# 3_channel_relay_board.net
KiCad netlist of a schematic drawn in EAGLE
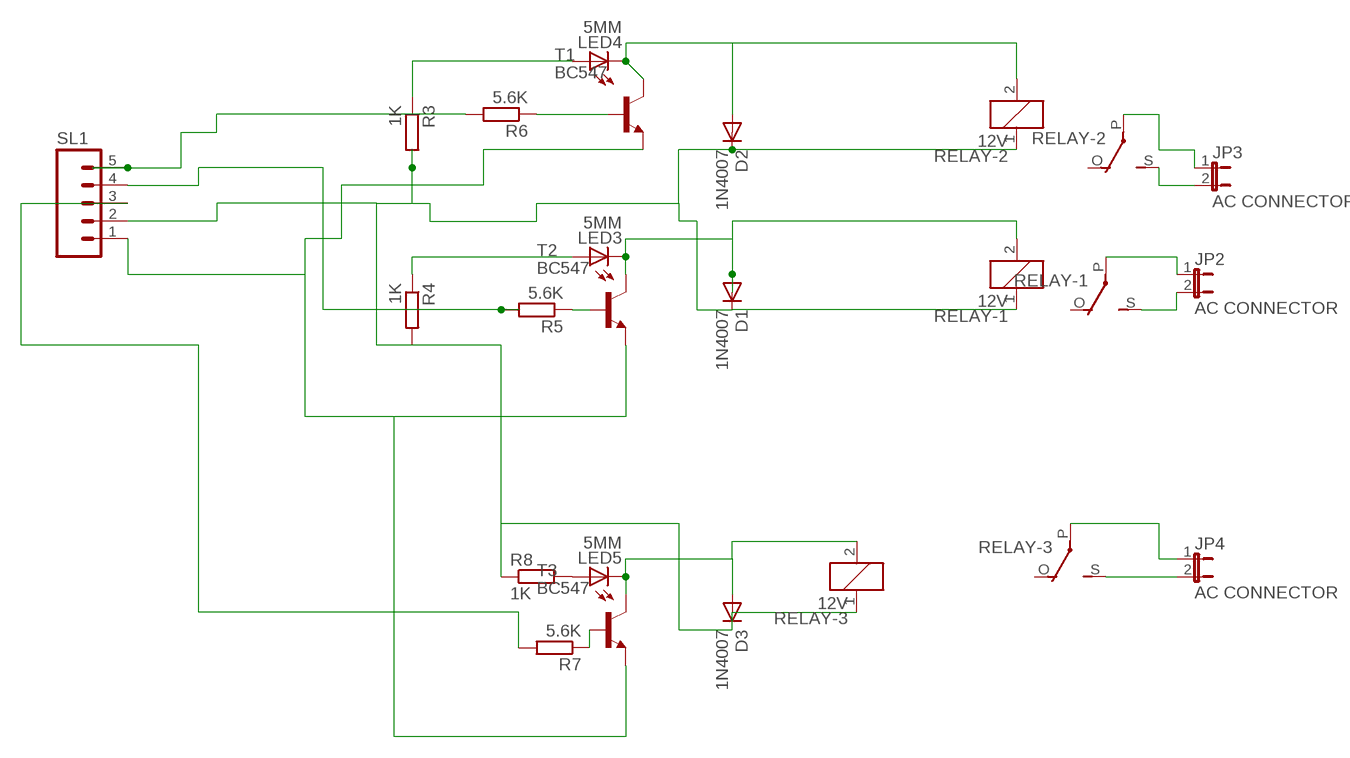
[diagram p0: schematic, sheet 1]

(export (version "E")
  (design (tool "Eeschema 10.0.6"))
  (components
    (comp (ref "D1")
      (value "1N4007")
      (footprint "eagle-import:DO41-10")
      (libsource (lib "eagle-import") (part "1N4004"))
    )
    (comp (ref "D2")
      (value "1N4007")
      (footprint "eagle-import:DO41-10")
      (libsource (lib "eagle-import") (part "1N4004"))
    )
    (comp (ref "D3")
      (value "1N4007")
      (footprint "eagle-import:DO41-10")
      (libsource (lib "eagle-import") (part "1N4004"))
    )
    (comp (ref "JP2")
      (value "AC CONNECTOR")
      (footprint "eagle-import:JP1")
      (libsource (lib "eagle-import") (part "JP1E"))
    )
    (comp (ref "JP3")
      (value "AC CONNECTOR")
      (footprint "eagle-import:JP1")
      (libsource (lib "eagle-import") (part "JP1E"))
    )
    (comp (ref "JP4")
      (value "AC CONNECTOR")
      (footprint "eagle-import:JP1")
      (libsource (lib "eagle-import") (part "JP1E"))
    )
    (comp (ref "LED3")
      (value "5MM")
      (footprint "eagle-import:LED5MM")
      (libsource (lib "eagle-import") (part "LED5MM"))
    )
    (comp (ref "LED4")
      (value "5MM")
      (footprint "eagle-import:LED5MM")
      (libsource (lib "eagle-import") (part "LED5MM"))
    )
    (comp (ref "LED5")
      (value "5MM")
      (footprint "eagle-import:LED5MM")
      (libsource (lib "eagle-import") (part "LED5MM"))
    )
    (comp (ref "R3")
      (value "1K")
      (footprint "eagle-import:0204_7")
      (libsource (lib "eagle-import") (part "R-EU_0204/7"))
    )
    (comp (ref "R4")
      (value "1K")
      (footprint "eagle-import:0204_7")
      (libsource (lib "eagle-import") (part "R-EU_0204/7"))
    )
    (comp (ref "R5")
      (value "5.6K")
      (footprint "eagle-import:0204_7")
      (libsource (lib "eagle-import") (part "R-EU_0204/7"))
    )
    (comp (ref "R6")
      (value "5.6K")
      (footprint "eagle-import:0204_7")
      (libsource (lib "eagle-import") (part "R-EU_0204/7"))
    )
    (comp (ref "R7")
      (value "5.6K")
      (footprint "eagle-import:0204_7")
      (libsource (lib "eagle-import") (part "R-EU_0204/7"))
    )
    (comp (ref "R8")
      (value "1K")
      (footprint "eagle-import:0204_7")
      (libsource (lib "eagle-import") (part "R-EU_0204/7"))
    )
    (comp (ref "RELAY-1")
      (value "12V")
      (footprint "eagle-import:G5LE")
      (libsource (lib "eagle-import") (part "G5L"))
    )
    (comp (ref "RELAY-2")
      (value "12V")
      (footprint "eagle-import:G5LE")
      (libsource (lib "eagle-import") (part "G5L"))
    )
    (comp (ref "RELAY-3")
      (value "12V")
      (footprint "eagle-import:G5LE")
      (fields (field (name "OC_FARNELL") "unknown") (field (name "OC_NEWARK") "unknown"))
      (libsource (lib "eagle-import") (part "G5L"))
    )
    (comp (ref "SL1")
      (value "M05")
      (footprint "eagle-import:05P")
      (libsource (lib "eagle-import") (part "M05"))
    )
    (comp (ref "T1")
      (value "BC547")
      (footprint "eagle-import:TO92")
      (libsource (lib "eagle-import") (part "BC547"))
    )
    (comp (ref "T2")
      (value "BC547")
      (footprint "eagle-import:TO92")
      (libsource (lib "eagle-import") (part "BC547"))
    )
    (comp (ref "T3")
      (value "BC547")
      (footprint "eagle-import:TO92")
      (libsource (lib "eagle-import") (part "BC547"))
    )
  )
  (nets
    (net (code "1") (name "Net-(D1-PadC)") (class "Default")
      (node (ref "D1") (pin "C") (pinfunction "C_C") (pintype "passive"))
      (node (ref "D2") (pin "C") (pinfunction "C_C") (pintype "passive"))
      (node (ref "D3") (pin "C") (pinfunction "C_C") (pintype "passive"))
      (node (ref "R3") (pin "2") (pinfunction "2_2") (pintype "passive"))
      (node (ref "R4") (pin "2") (pinfunction "2_2") (pintype "passive"))
      (node (ref "R8") (pin "1") (pinfunction "1_1") (pintype "passive"))
      (node (ref "RELAY-1") (pin "1") (pinfunction "1_1") (pintype "passive"))
      (node (ref "RELAY-2") (pin "1") (pinfunction "1_1") (pintype "passive"))
      (node (ref "RELAY-3") (pin "1") (pinfunction "1_1") (pintype "passive"))
      (node (ref "SL1") (pin "2") (pinfunction "2_2") (pintype "passive"))
    )
    (net (code "2") (name "Net-(JP2-Pad1)") (class "Default")
      (node (ref "JP2") (pin "1") (pinfunction "1_1") (pintype "passive"))
      (node (ref "RELAY-1") (pin "P") (pinfunction "P_P") (pintype "passive"))
    )
    (net (code "3") (name "Net-(JP2-Pad2)") (class "Default")
      (node (ref "JP2") (pin "2") (pinfunction "2_2") (pintype "passive"))
      (node (ref "RELAY-1") (pin "S") (pinfunction "S_S") (pintype "passive"))
    )
    (net (code "4") (name "Net-(JP3-Pad1)") (class "Default")
      (node (ref "JP3") (pin "1") (pinfunction "1_1") (pintype "passive"))
      (node (ref "RELAY-2") (pin "P") (pinfunction "P_P") (pintype "passive"))
    )
    (net (code "5") (name "Net-(JP3-Pad2)") (class "Default")
      (node (ref "JP3") (pin "2") (pinfunction "2_2") (pintype "passive"))
      (node (ref "RELAY-2") (pin "S") (pinfunction "S_S") (pintype "passive"))
    )
    (net (code "6") (name "Net-(JP4-Pad1)") (class "Default")
      (node (ref "JP4") (pin "1") (pinfunction "1_1") (pintype "passive"))
      (node (ref "RELAY-3") (pin "P") (pinfunction "P_P") (pintype "passive"))
    )
    (net (code "7") (name "Net-(JP4-Pad2)") (class "Default")
      (node (ref "JP4") (pin "2") (pinfunction "2_2") (pintype "passive"))
      (node (ref "RELAY-3") (pin "S") (pinfunction "S_S") (pintype "passive"))
    )
    (net (code "8") (name "Net-(LED3-C)") (class "Default")
      (node (ref "D1") (pin "A") (pinfunction "A_A") (pintype "passive"))
      (node (ref "LED3") (pin "K") (pinfunction "C_K") (pintype "passive"))
      (node (ref "RELAY-1") (pin "2") (pinfunction "2_2") (pintype "passive"))
      (node (ref "T2") (pin "3") (pinfunction "C_3") (pintype "passive"))
    )
    (net (code "9") (name "Net-(LED3-PadA)") (class "Default")
      (node (ref "LED3") (pin "A") (pinfunction "A_A") (pintype "passive"))
      (node (ref "R4") (pin "1") (pinfunction "1_1") (pintype "passive"))
    )
    (net (code "10") (name "Net-(LED4-C)") (class "Default")
      (node (ref "D2") (pin "A") (pinfunction "A_A") (pintype "passive"))
      (node (ref "LED4") (pin "K") (pinfunction "C_K") (pintype "passive"))
      (node (ref "RELAY-2") (pin "2") (pinfunction "2_2") (pintype "passive"))
      (node (ref "T1") (pin "3") (pinfunction "C_3") (pintype "passive"))
    )
    (net (code "11") (name "Net-(LED4-PadA)") (class "Default")
      (node (ref "LED4") (pin "A") (pinfunction "A_A") (pintype "passive"))
      (node (ref "R3") (pin "1") (pinfunction "1_1") (pintype "passive"))
    )
    (net (code "12") (name "Net-(LED5-C)") (class "Default")
      (node (ref "D3") (pin "A") (pinfunction "A_A") (pintype "passive"))
      (node (ref "LED5") (pin "K") (pinfunction "C_K") (pintype "passive"))
      (node (ref "RELAY-3") (pin "2") (pinfunction "2_2") (pintype "passive"))
      (node (ref "T3") (pin "3") (pinfunction "C_3") (pintype "passive"))
    )
    (net (code "13") (name "Net-(LED5-PadA)") (class "Default")
      (node (ref "LED5") (pin "A") (pinfunction "A_A") (pintype "passive"))
      (node (ref "R8") (pin "2") (pinfunction "2_2") (pintype "passive"))
    )
    (net (code "14") (name "Net-(R5-Pad2)") (class "Default")
      (node (ref "R5") (pin "2") (pinfunction "2_2") (pintype "passive"))
      (node (ref "SL1") (pin "4") (pinfunction "4_4") (pintype "passive"))
    )
    (net (code "15") (name "Net-(R6-Pad2)") (class "Default")
      (node (ref "R6") (pin "2") (pinfunction "2_2") (pintype "passive"))
      (node (ref "SL1") (pin "5") (pinfunction "5_5") (pintype "passive"))
    )
    (net (code "16") (name "Net-(R7-Pad2)") (class "Default")
      (node (ref "R7") (pin "2") (pinfunction "2_2") (pintype "passive"))
      (node (ref "SL1") (pin "3") (pinfunction "3_3") (pintype "passive"))
    )
    (net (code "17") (name "Net-(T1-B)") (class "Default")
      (node (ref "R6") (pin "1") (pinfunction "1_1") (pintype "passive"))
      (node (ref "T1") (pin "2") (pinfunction "B_2") (pintype "passive"))
    )
    (net (code "18") (name "Net-(T1-E)") (class "Default")
      (node (ref "SL1") (pin "1") (pinfunction "1_1") (pintype "passive"))
      (node (ref "T1") (pin "1") (pinfunction "E_1") (pintype "passive"))
      (node (ref "T2") (pin "1") (pinfunction "E_1") (pintype "passive"))
      (node (ref "T3") (pin "1") (pinfunction "E_1") (pintype "passive"))
    )
    (net (code "19") (name "Net-(T2-B)") (class "Default")
      (node (ref "R5") (pin "1") (pinfunction "1_1") (pintype "passive"))
      (node (ref "T2") (pin "2") (pinfunction "B_2") (pintype "passive"))
    )
    (net (code "20") (name "Net-(T3-B)") (class "Default")
      (node (ref "R7") (pin "1") (pinfunction "1_1") (pintype "passive"))
      (node (ref "T3") (pin "2") (pinfunction "B_2") (pintype "passive"))
    )
    (net (code "21") (name "unconnected-(RELAY-1-PadO)") (class "Default")
      (node (ref "RELAY-1") (pin "O") (pinfunction "O_O") (pintype "passive"))
    )
    (net (code "22") (name "unconnected-(RELAY-2-PadO)") (class "Default")
      (node (ref "RELAY-2") (pin "O") (pinfunction "O_O") (pintype "passive"))
    )
    (net (code "23") (name "unconnected-(RELAY-3-PadO)") (class "Default")
      (node (ref "RELAY-3") (pin "O") (pinfunction "O_O") (pintype "passive"))
    )
  )
)
